# MotorControllerMainBoard.net
KiCad netlist of a schematic drawn in EAGLE
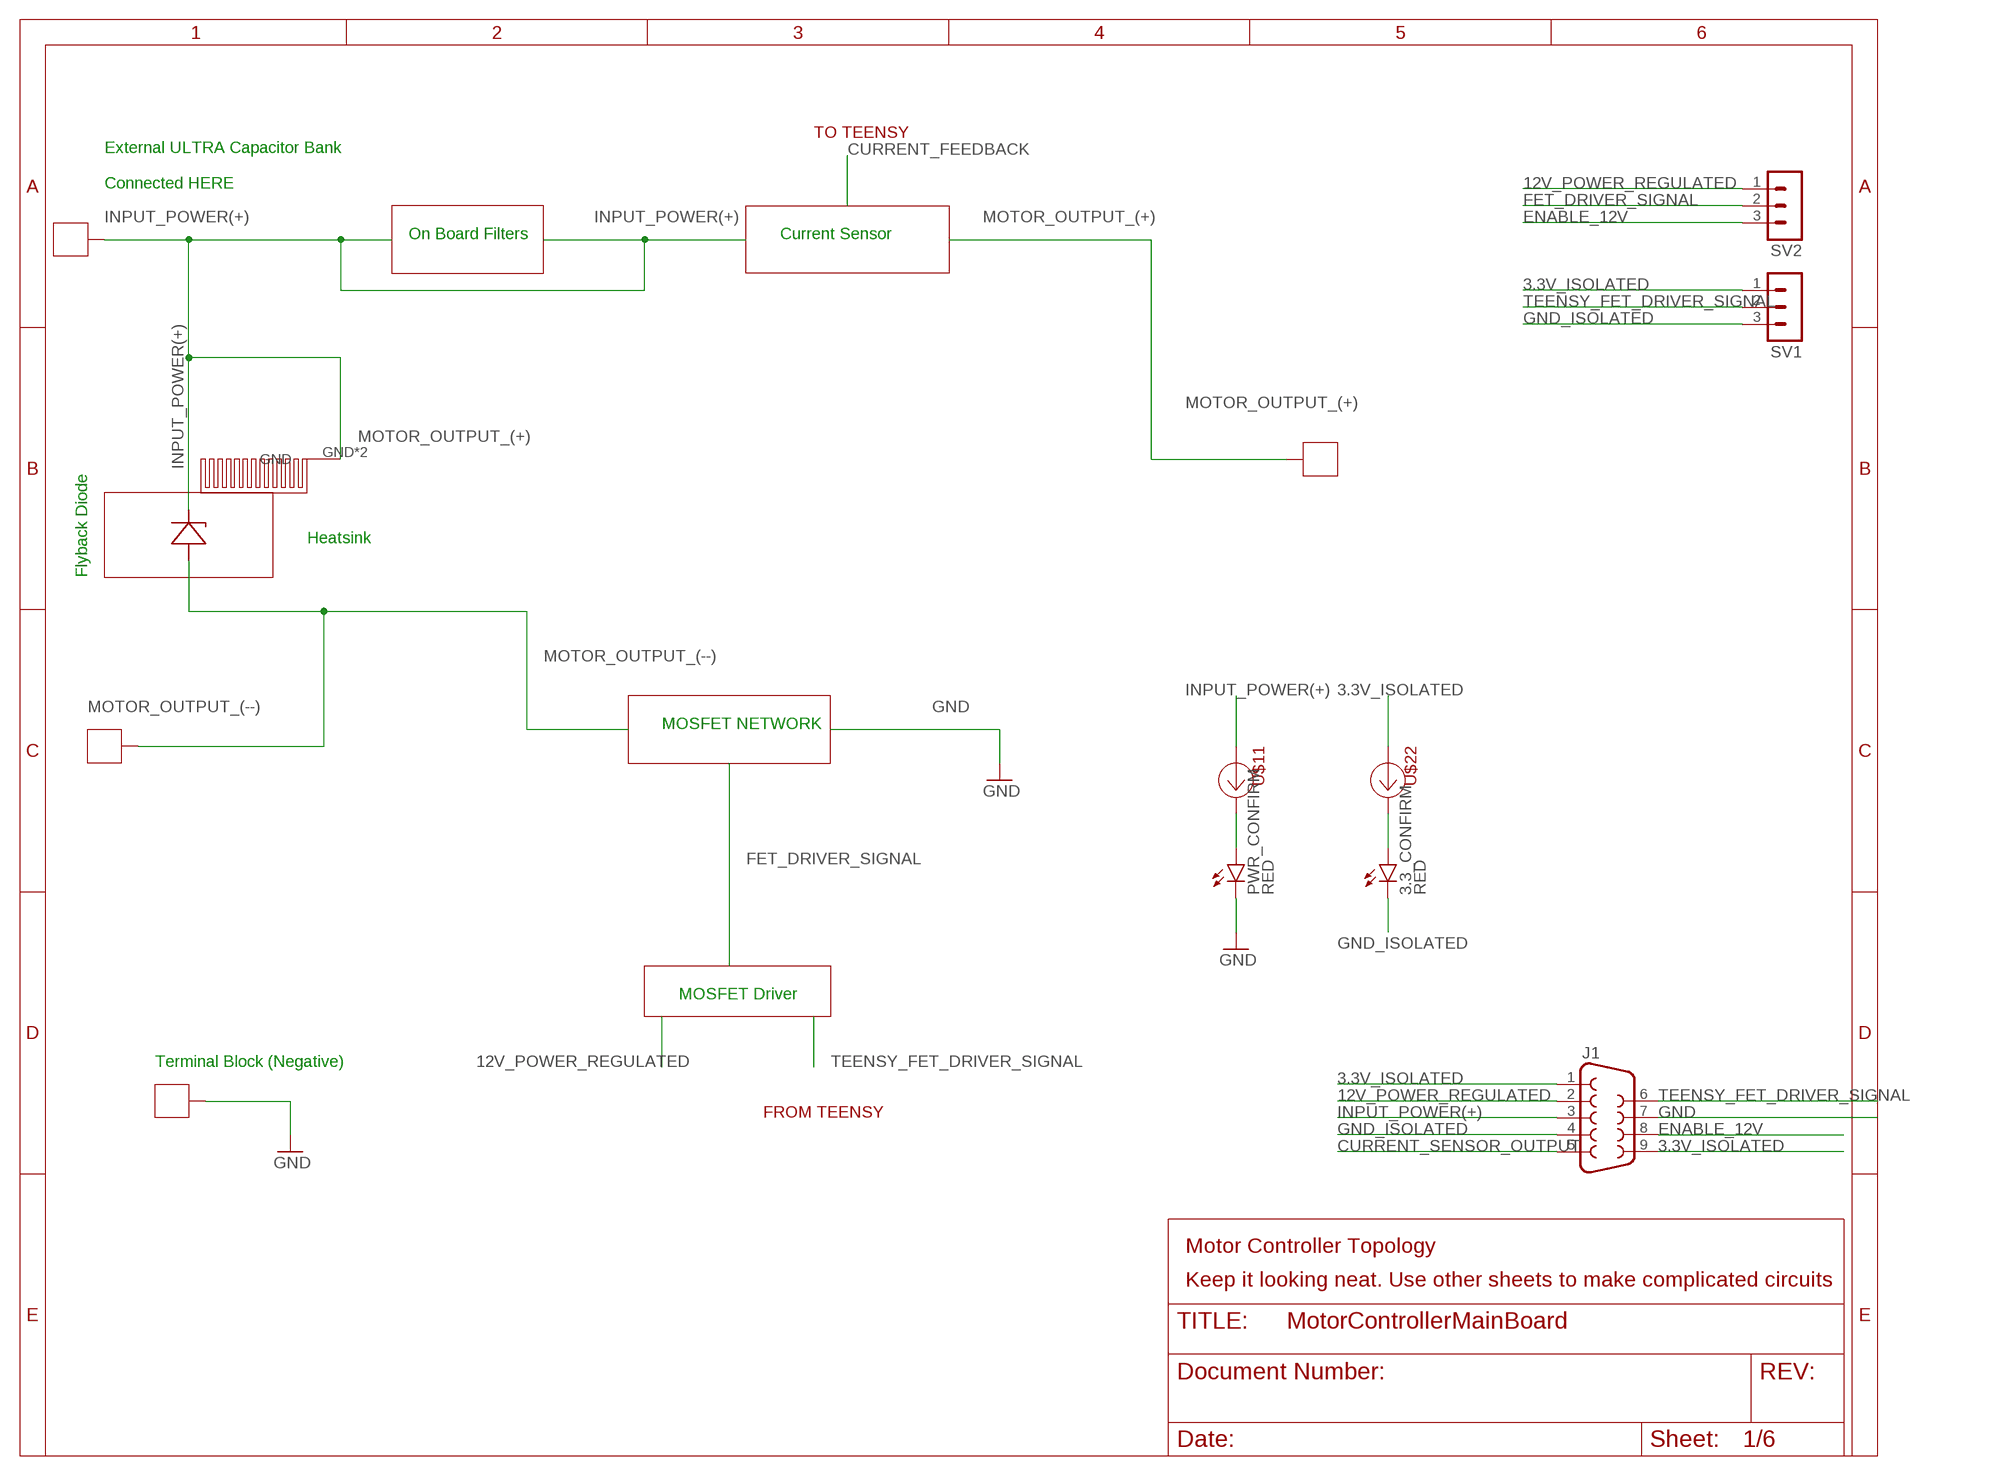
[diagram p0: schematic, sheet 1]
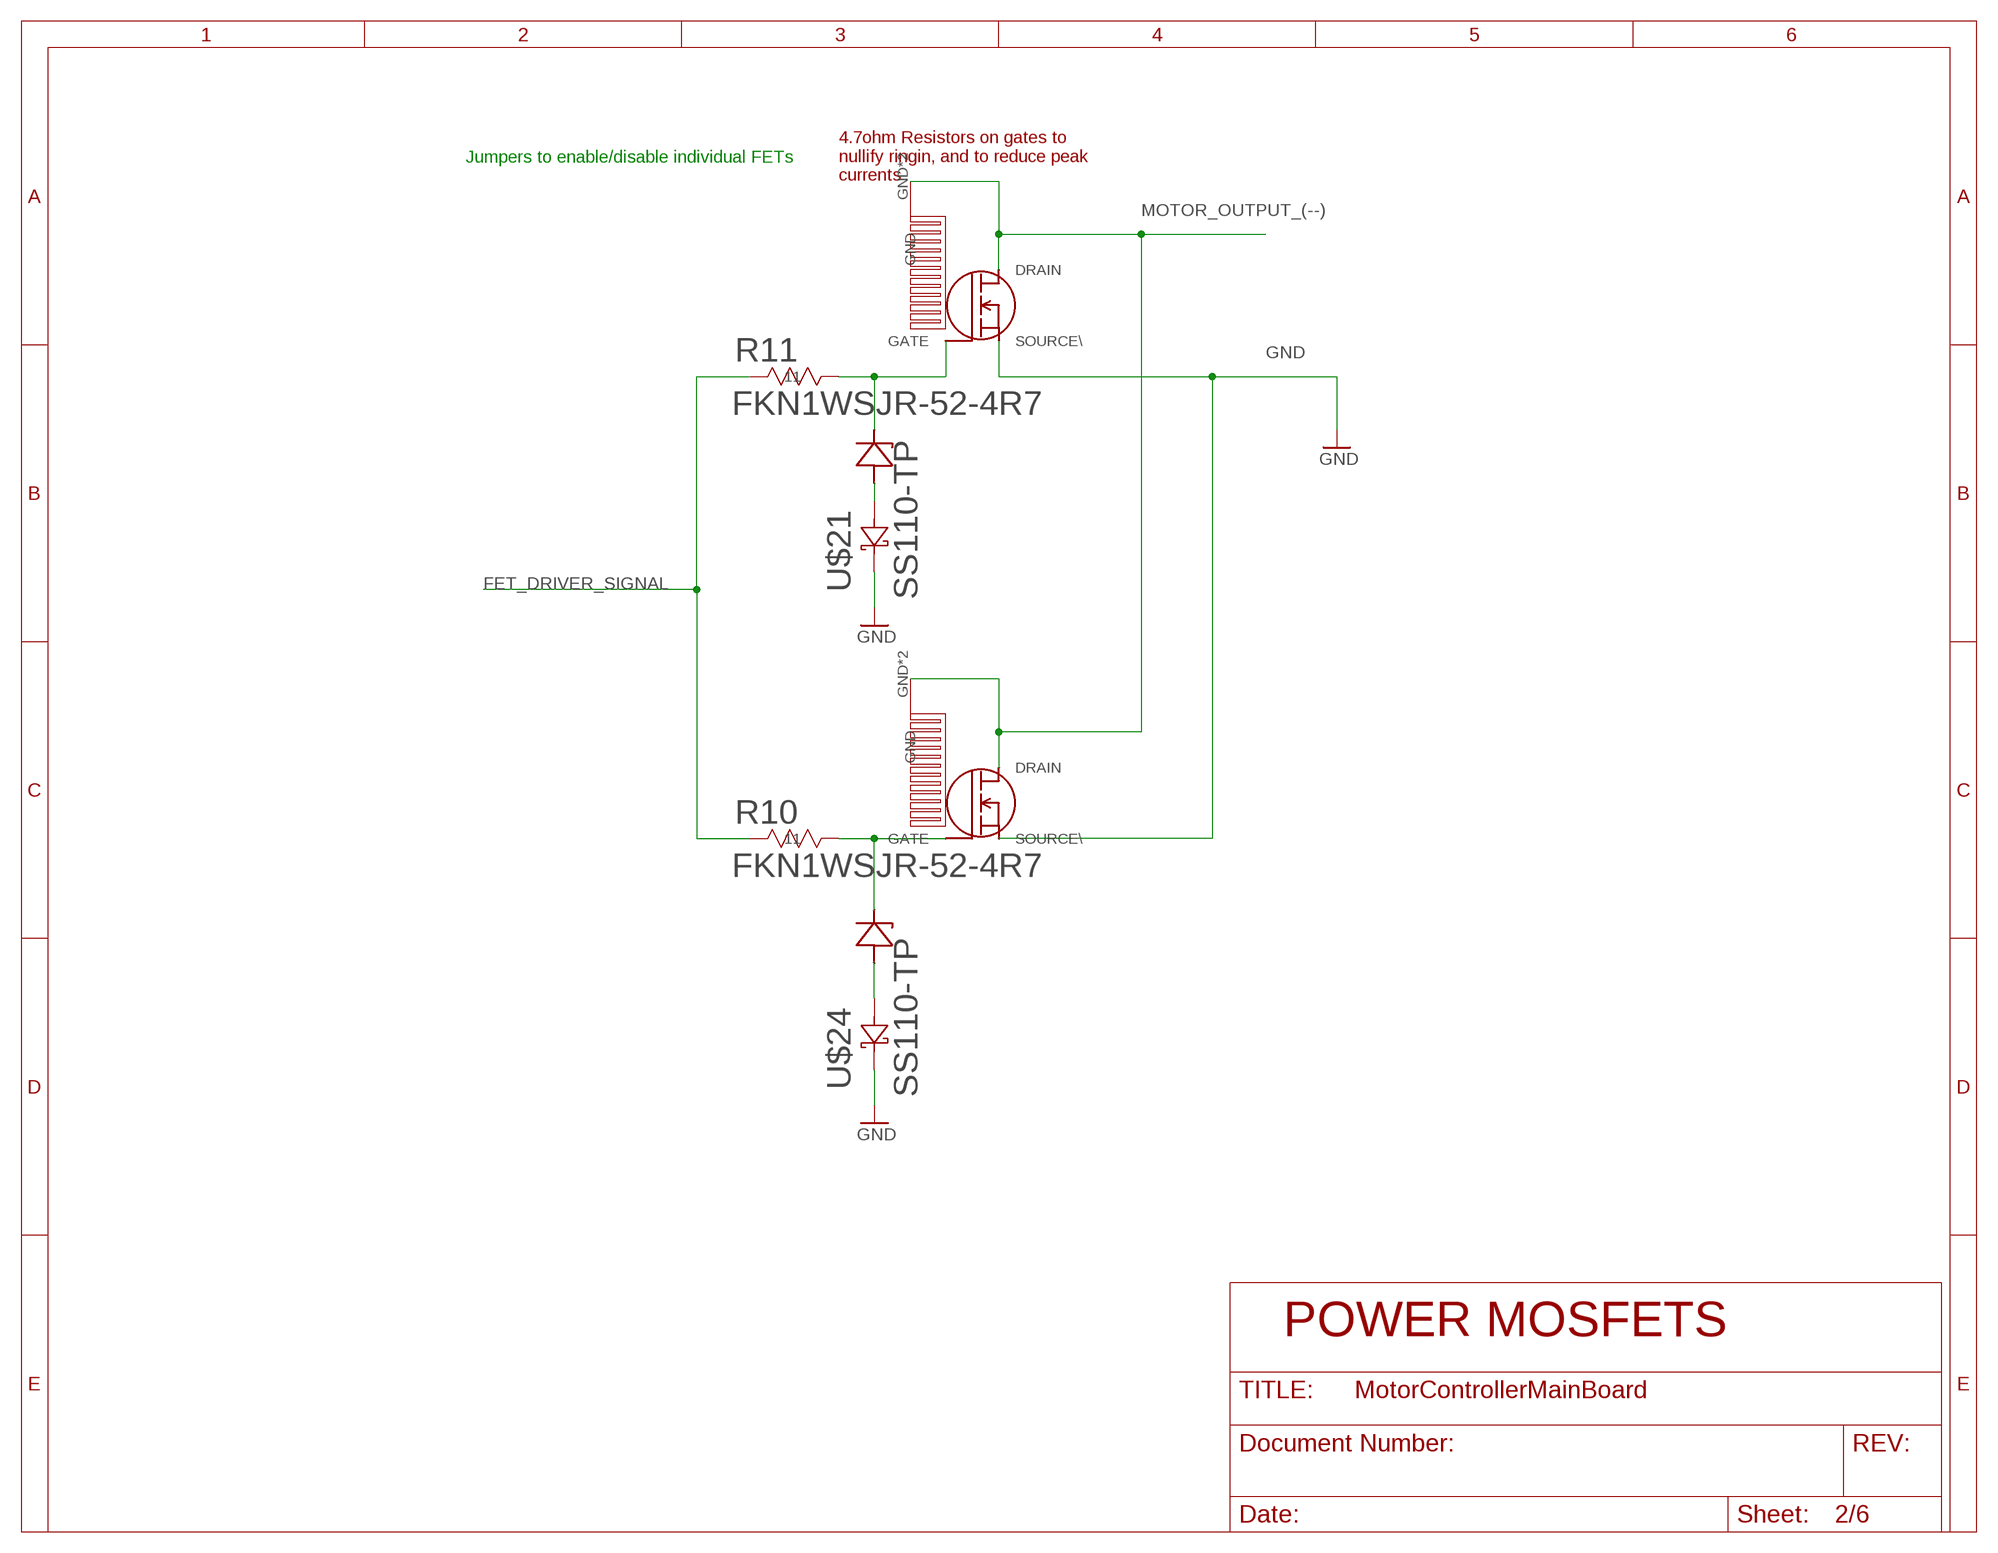
[diagram p1: schematic, sheet 2]
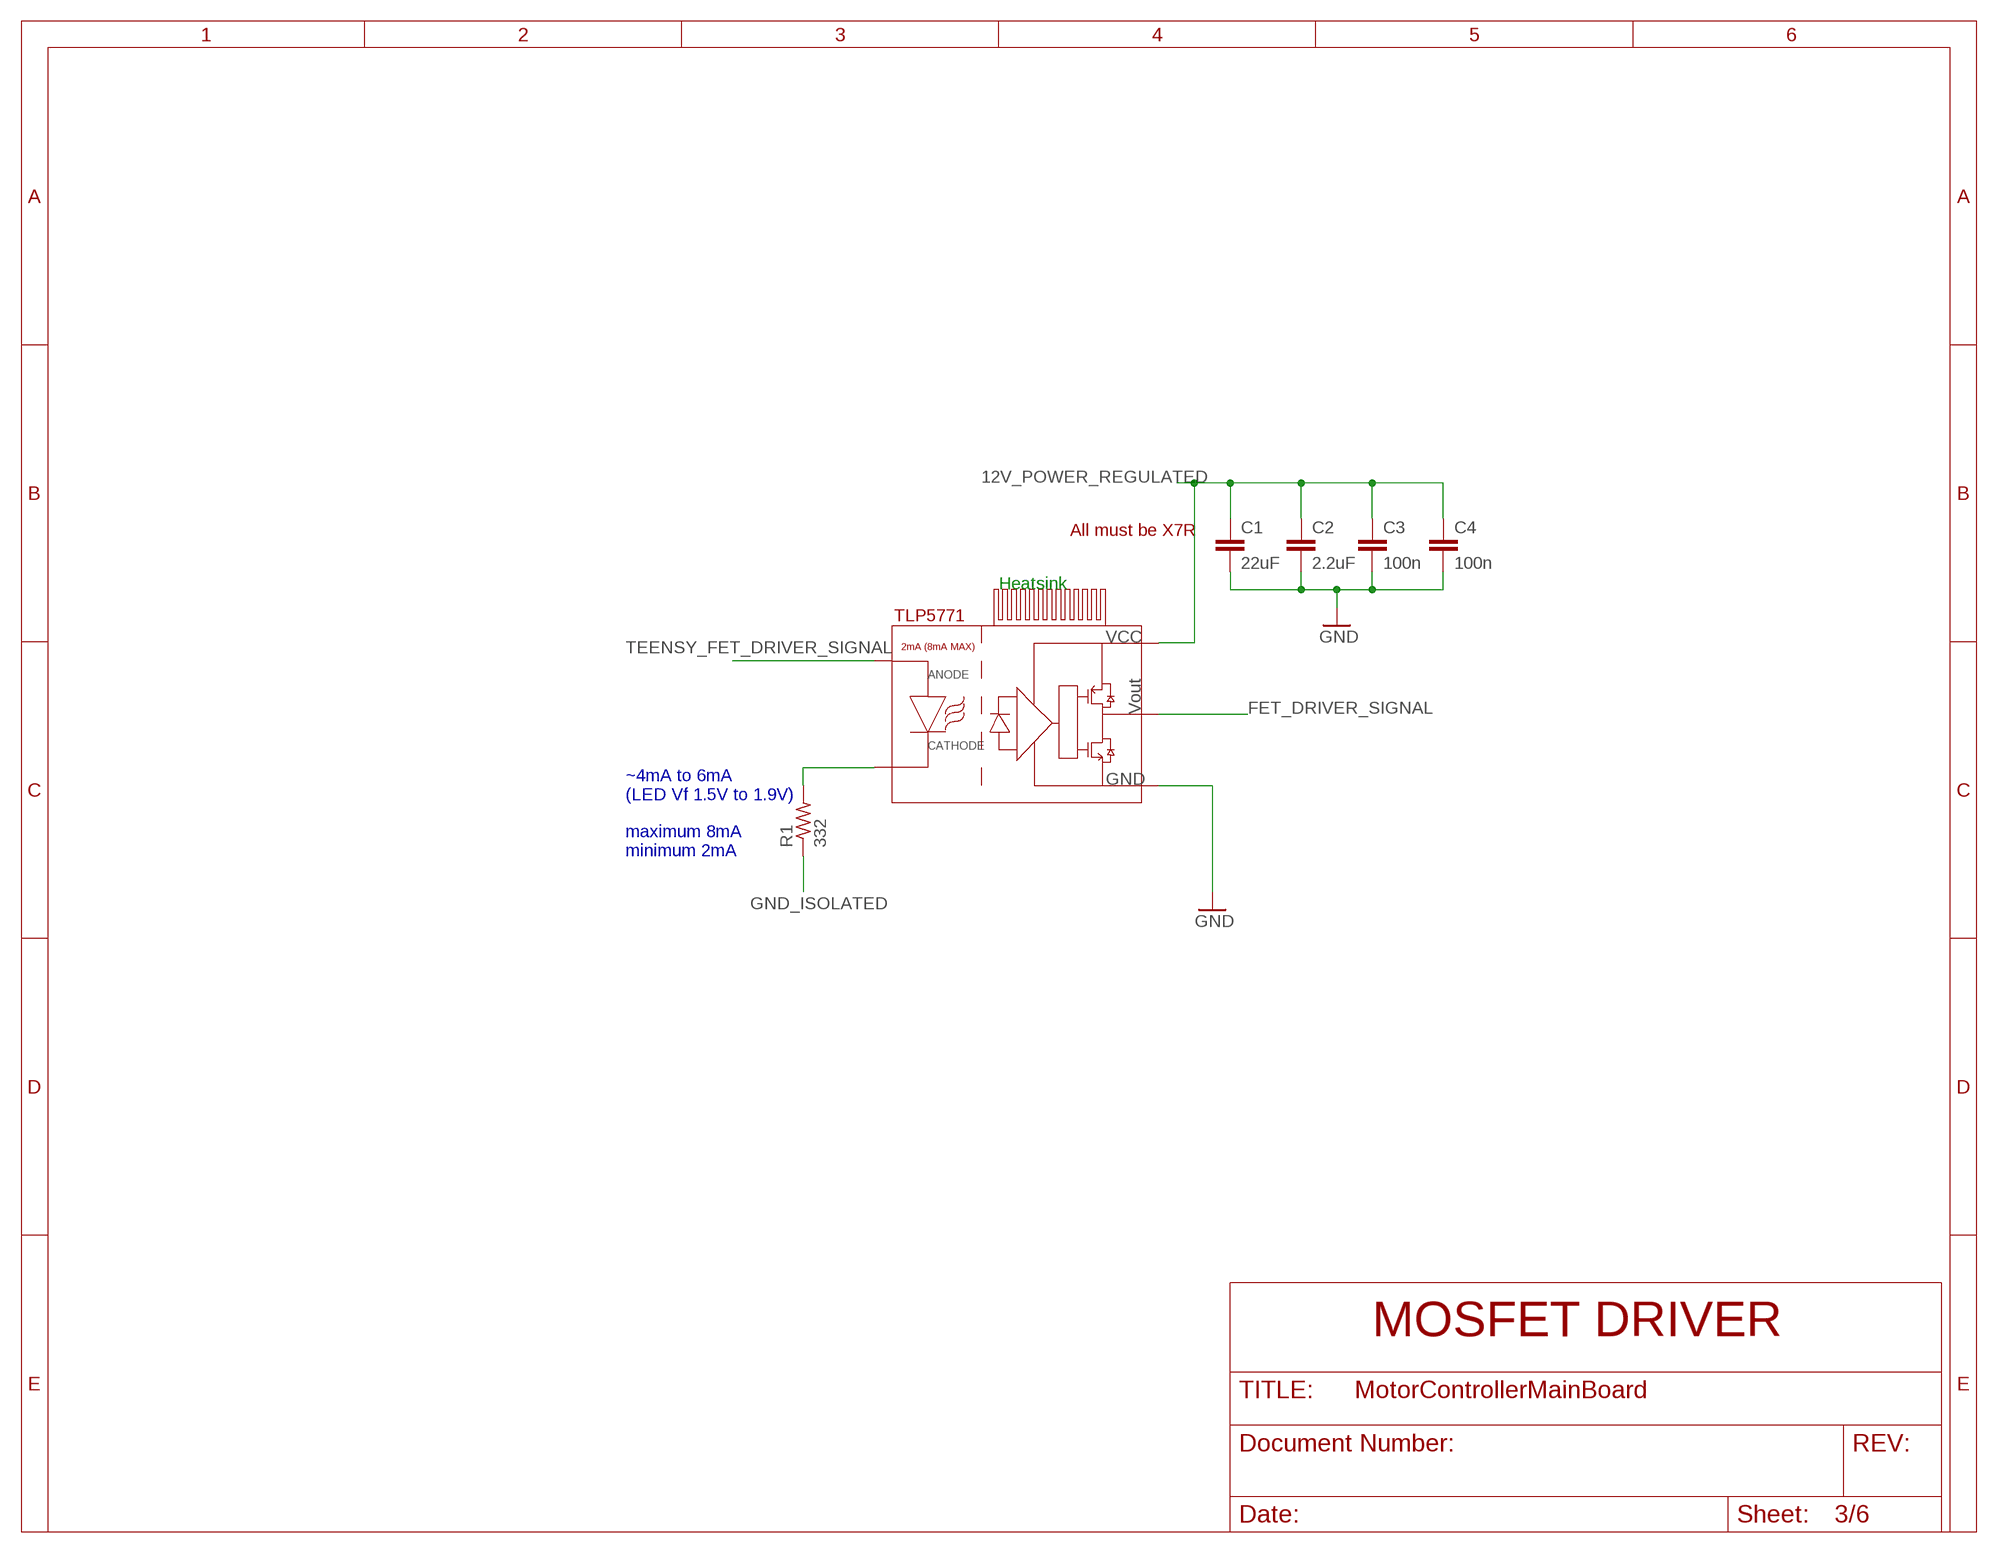
[diagram p2: schematic, sheet 3]
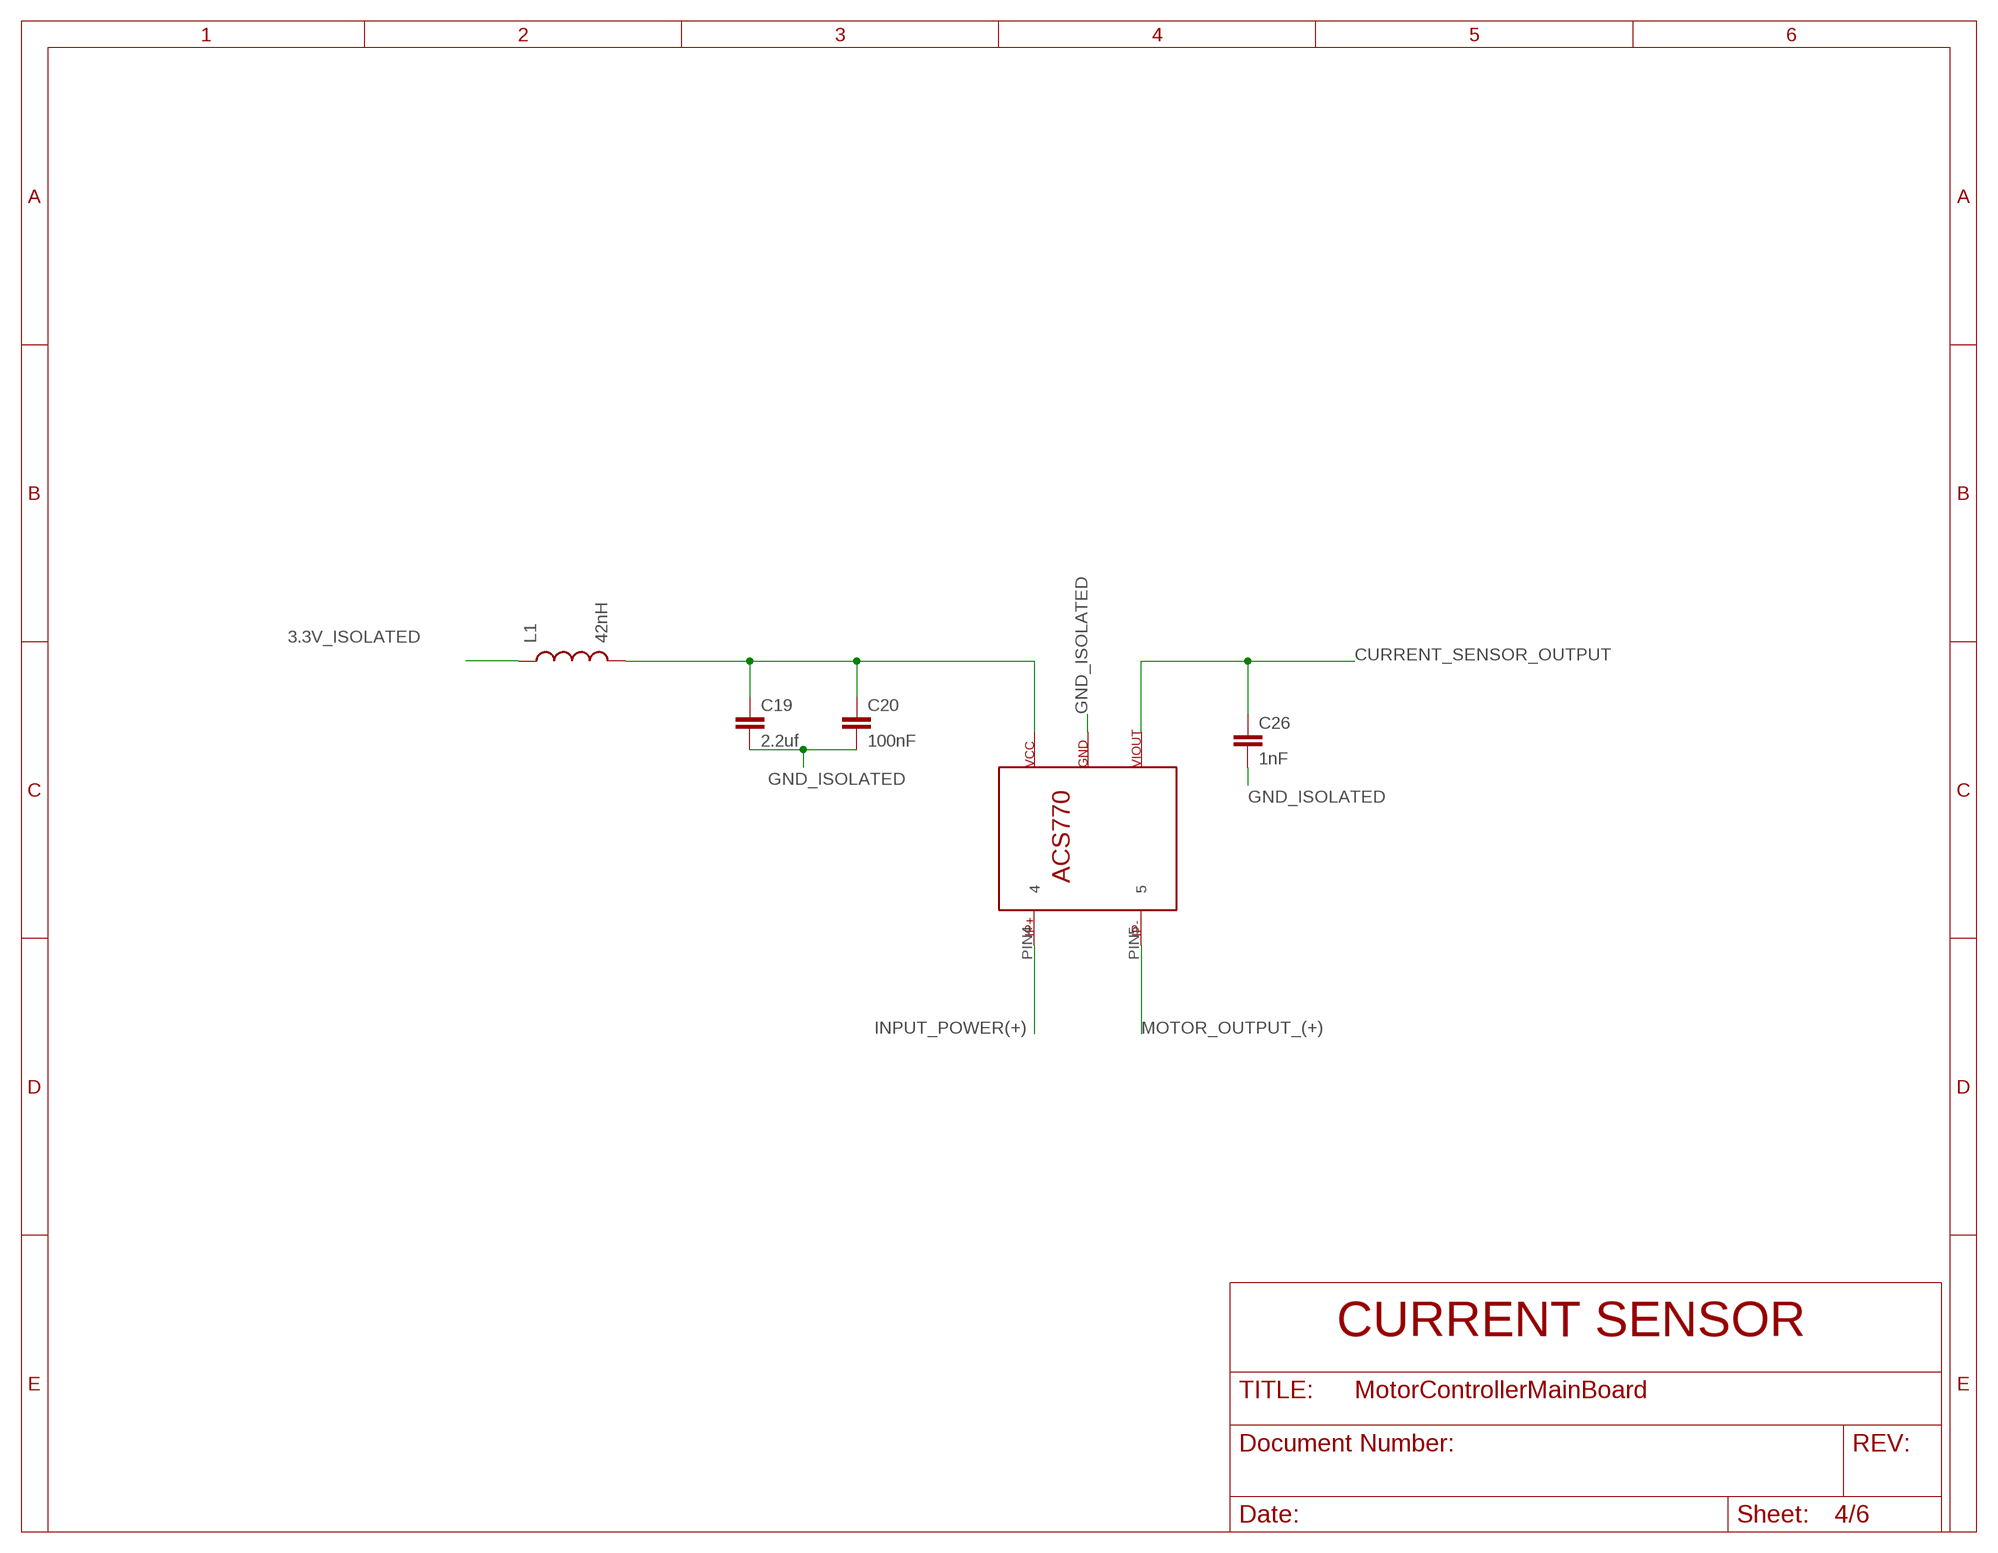
[diagram p3: schematic, sheet 4]
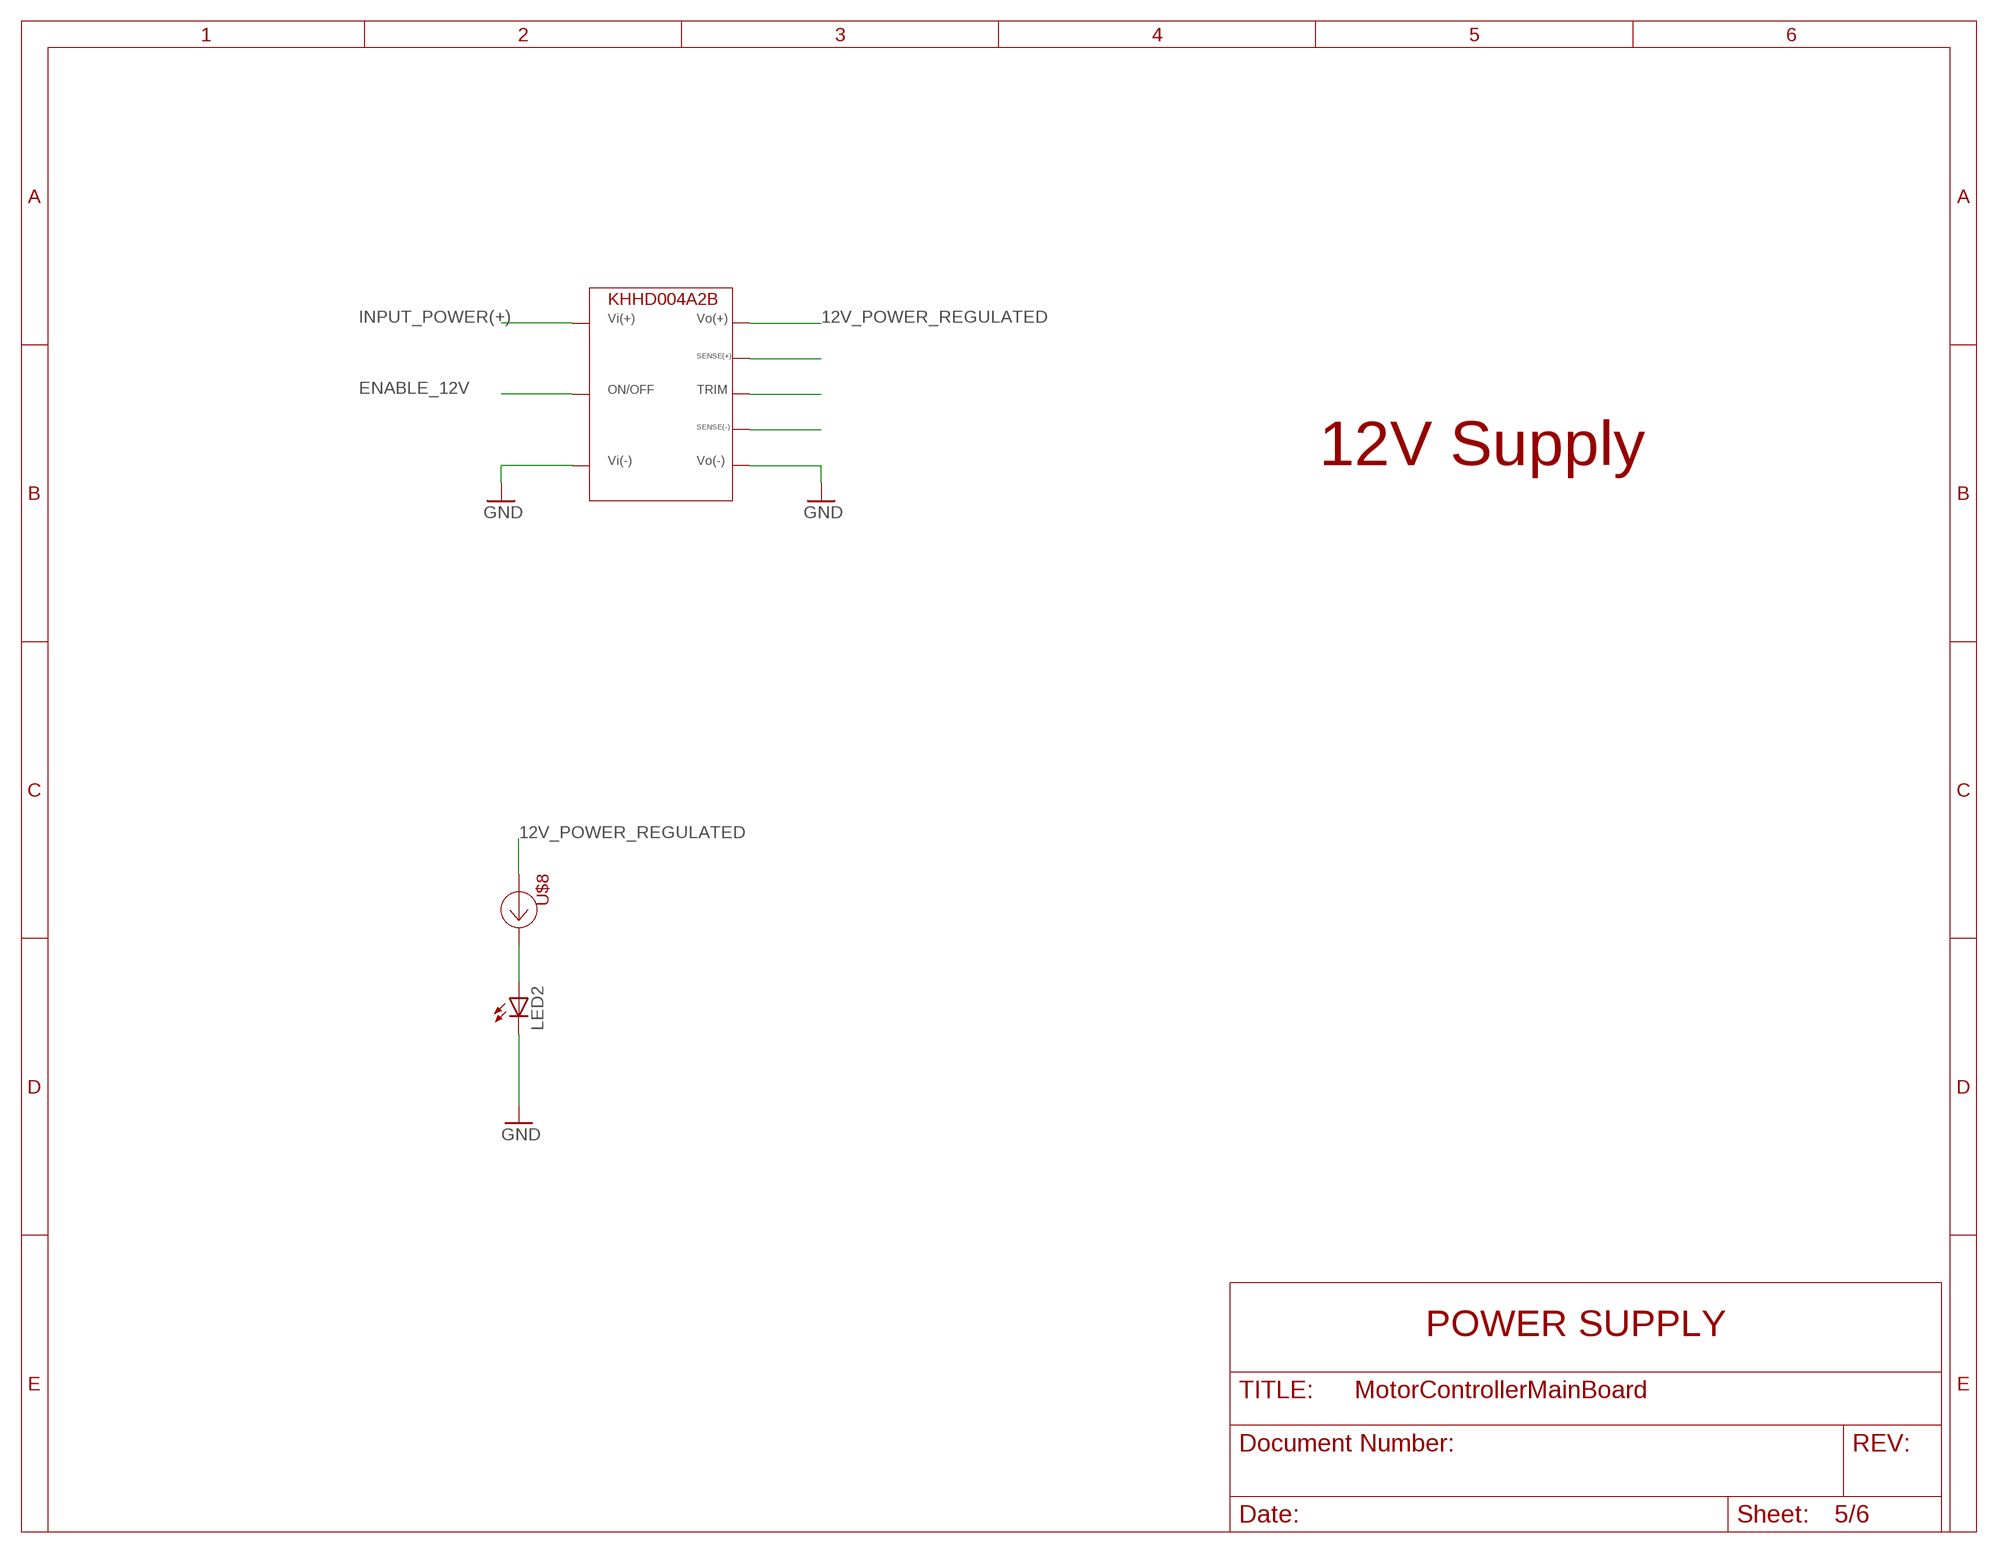
[diagram p4: schematic, sheet 5]
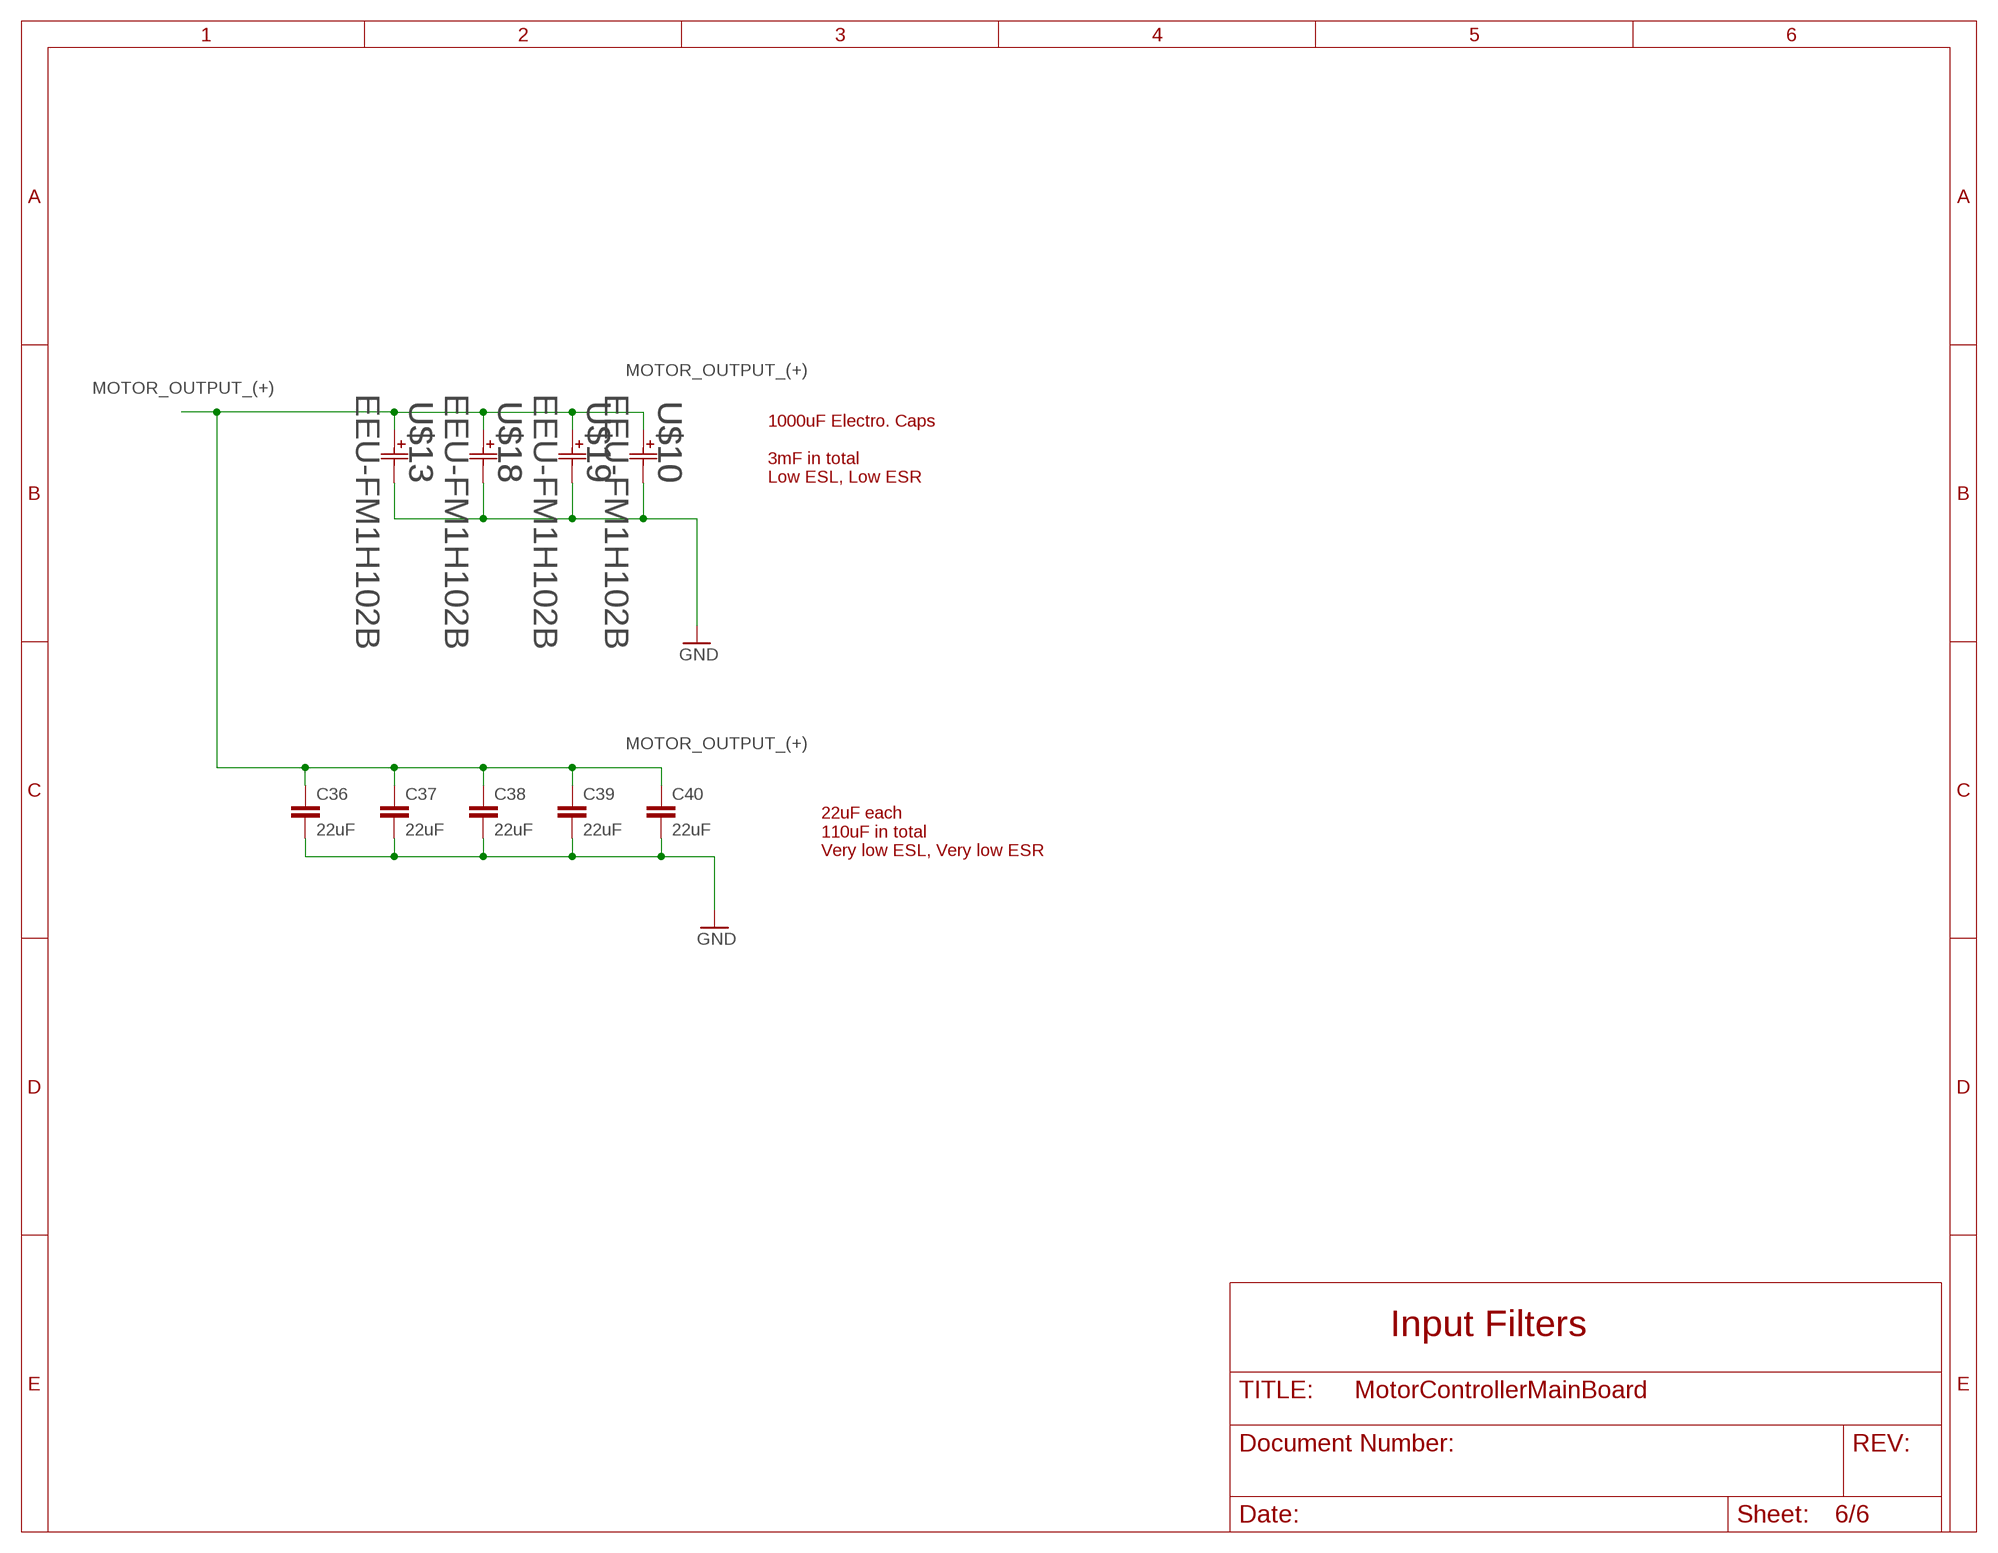
[diagram p5: schematic, sheet 6]

(export (version "E")
  (design (tool "Eeschema 10.0.6"))
  (components
    (comp (ref "3.3_CONFIRM")
      (value "RED")
      (footprint "eagle-import:LED-1206")
      (libsource (lib "eagle-import") (part "LED-RED1206"))
    )
    (comp (ref "J1")
      (value "DB9FEMALE")
      (footprint "eagle-import:DB9")
      (libsource (lib "eagle-import") (part "DB9FEMALE"))
    )
    (comp (ref "PWR_CONFIRM")
      (value "RED")
      (footprint "eagle-import:LED-1206")
      (libsource (lib "eagle-import") (part "LED-RED1206"))
    )
    (comp (ref "SV1")
      (value "MA03-1")
      (footprint "eagle-import:MA03-1")
      (libsource (lib "eagle-import") (part "MA03-1"))
    )
    (comp (ref "SV2")
      (value "MA03-1")
      (footprint "eagle-import:MA03-1")
      (libsource (lib "eagle-import") (part "MA03-1"))
    )
    (comp (ref "U$5")
      (value "FLYBACK")
      (footprint "eagle-import:TO")
      (libsource (lib "eagle-import") (part "FLYBACK"))
    )
    (comp (ref "U$11")
      (value "AL5809-20S1-7")
      (footprint "eagle-import:SOD-123")
      (libsource (lib "eagle-import") (part "AL5809-20S1-7"))
    )
    (comp (ref "U$12")
      (value "74650073R")
      (footprint "eagle-import:74650073R")
      (libsource (lib "eagle-import") (part "74650073R"))
    )
    (comp (ref "U$14")
      (value "74650073R")
      (footprint "eagle-import:74650073R")
      (libsource (lib "eagle-import") (part "74650073R"))
    )
    (comp (ref "U$15")
      (value "74650073R")
      (footprint "eagle-import:74650073R")
      (libsource (lib "eagle-import") (part "74650073R"))
    )
    (comp (ref "U$16")
      (value "74650073R")
      (footprint "eagle-import:74650073R")
      (libsource (lib "eagle-import") (part "74650073R"))
    )
    (comp (ref "U$22")
      (value "AL5809-20S1-7")
      (footprint "eagle-import:SOD-123")
      (libsource (lib "eagle-import") (part "AL5809-20S1-7"))
    )
    (comp (ref "U$23")
      (value "DA-T263-101E")
      (footprint "eagle-import:DA-T263-101E")
      (libsource (lib "eagle-import") (part "DA-T263-101E"))
    )
    (comp (ref "C36")
      (value "22uF")
      (footprint "eagle-import:C1210")
      (libsource (lib "eagle-import") (part "C-EUC1210"))
    )
    (comp (ref "C37")
      (value "22uF")
      (footprint "eagle-import:C1210")
      (libsource (lib "eagle-import") (part "C-EUC1210"))
    )
    (comp (ref "C38")
      (value "22uF")
      (footprint "eagle-import:C1210")
      (libsource (lib "eagle-import") (part "C-EUC1210"))
    )
    (comp (ref "C39")
      (value "22uF")
      (footprint "eagle-import:C1210")
      (libsource (lib "eagle-import") (part "C-EUC1210"))
    )
    (comp (ref "C40")
      (value "22uF")
      (footprint "eagle-import:C1210")
      (libsource (lib "eagle-import") (part "C-EUC1210"))
    )
    (comp (ref "U$10")
      (value "EEU-FM1H102B")
      (footprint "eagle-import:EEU-FM1H102B")
      (libsource (lib "eagle-import") (part "EEU-FM1H102B"))
    )
    (comp (ref "U$13")
      (value "EEU-FM1H102B")
      (footprint "eagle-import:EEU-FM1H102B")
      (libsource (lib "eagle-import") (part "EEU-FM1H102B"))
    )
    (comp (ref "U$18")
      (value "EEU-FM1H102B")
      (footprint "eagle-import:EEU-FM1H102B")
      (libsource (lib "eagle-import") (part "EEU-FM1H102B"))
    )
    (comp (ref "U$19")
      (value "EEU-FM1H102B")
      (footprint "eagle-import:EEU-FM1H102B")
      (libsource (lib "eagle-import") (part "EEU-FM1H102B"))
    )
    (comp (ref "LED2")
      (value "LED1206")
      (footprint "eagle-import:LED-1206")
      (libsource (lib "eagle-import") (part "LED1206"))
    )
    (comp (ref "U$6")
      (value "KHHD004A2B")
      (footprint "eagle-import:KHHD004A2B")
      (libsource (lib "eagle-import") (part "KHHD004A2B"))
    )
    (comp (ref "U$8")
      (value "AL5809-20S1-7")
      (footprint "eagle-import:SOD-123")
      (libsource (lib "eagle-import") (part "AL5809-20S1-7"))
    )
    (comp (ref "C1")
      (value "22uF")
      (footprint "eagle-import:C1210")
      (libsource (lib "eagle-import") (part "C-EUC1210"))
    )
    (comp (ref "C2")
      (value "2.2uF")
      (footprint "eagle-import:C0805")
      (libsource (lib "eagle-import") (part "C-EUC0805"))
    )
    (comp (ref "C3")
      (value "100n")
      (footprint "eagle-import:C0603")
      (libsource (lib "eagle-import") (part "C-EUC0603"))
    )
    (comp (ref "C4")
      (value "100n")
      (footprint "eagle-import:C0603")
      (libsource (lib "eagle-import") (part "C-EUC0603"))
    )
    (comp (ref "R1")
      (value "332")
      (footprint "eagle-import:R0805")
      (libsource (lib "eagle-import") (part "R-US_R0805"))
    )
    (comp (ref "U$17")
      (value "TLP5771")
      (footprint "eagle-import:SOIC-6(TLP5771)")
      (libsource (lib "eagle-import") (part "TLP5771"))
    )
    (comp (ref "U$25")
      (value "LTN20069")
      (footprint "eagle-import:LTN20069")
      (libsource (lib "eagle-import") (part "LTN20069"))
    )
    (comp (ref "C19")
      (value "2.2uf")
      (footprint "eagle-import:C0805")
      (libsource (lib "eagle-import") (part "resistor_348_C-EUC0805"))
    )
    (comp (ref "C20")
      (value "100nF")
      (footprint "eagle-import:C0805")
      (libsource (lib "eagle-import") (part "resistor_348_C-EUC0805"))
    )
    (comp (ref "C26")
      (value "1nF")
      (footprint "eagle-import:C0805")
      (libsource (lib "eagle-import") (part "resistor_348_C-EUC0805"))
    )
    (comp (ref "L1")
      (value "42nH")
      (footprint "eagle-import:0805")
      (libsource (lib "eagle-import") (part "INDUCTOR0805"))
    )
    (comp (ref "U$9")
      (value "ACS770LCB_CURRENTSENSOR")
      (footprint "eagle-import:ACS770LCB_CURRENTSENSOR")
      (libsource (lib "eagle-import") (part "ACS770LCB_CURRENTSENSOR"))
    )
    (comp (ref "R10")
      (value "FKN1WSJR-52-4R7")
      (footprint "eagle-import:YAG_FKN50")
      (fields (field (name "MANUFACTURER_PART_NUMBER") "FKN1WSJR524R7"))
      (libsource (lib "eagle-import") (part "FKN1WSJR-52-4R7"))
    )
    (comp (ref "R11")
      (value "FKN1WSJR-52-4R7")
      (footprint "eagle-import:YAG_FKN50")
      (fields (field (name "MANUFACTURER_PART_NUMBER") "FKN1WSJR524R7"))
      (libsource (lib "eagle-import") (part "FKN1WSJR-52-4R7"))
    )
    (comp (ref "U$1")
      (value "IPB015N08N5ATMA1")
      (footprint "eagle-import:IPB015N08N5ATMA1")
      (libsource (lib "eagle-import") (part "IPB015N08N5ATMA1"))
    )
    (comp (ref "U$2")
      (value "IPB015N08N5ATMA1")
      (footprint "eagle-import:IPB015N08N5ATMA1")
      (libsource (lib "eagle-import") (part "IPB015N08N5ATMA1"))
    )
    (comp (ref "U$3")
      (value "DA-T263-101E")
      (footprint "eagle-import:DA-T263-101E")
      (libsource (lib "eagle-import") (part "DA-T263-101E"))
    )
    (comp (ref "U$4")
      (value "DA-T263-101E")
      (footprint "eagle-import:DA-T263-101E")
      (libsource (lib "eagle-import") (part "DA-T263-101E"))
    )
    (comp (ref "U$7")
      (value "SMBJ15CD")
      (footprint "eagle-import:SMB-DIODE")
      (libsource (lib "eagle-import") (part "SMBJ15CD"))
    )
    (comp (ref "U$20")
      (value "SMBJ15CD")
      (footprint "eagle-import:SMB-DIODE")
      (libsource (lib "eagle-import") (part "SMBJ15CD"))
    )
    (comp (ref "U$21")
      (value "SS110-TP")
      (footprint "eagle-import:SMA-DIODE")
      (libsource (lib "eagle-import") (part "SS110-TP"))
    )
    (comp (ref "U$24")
      (value "SS110-TP")
      (footprint "eagle-import:SMA-DIODE")
      (libsource (lib "eagle-import") (part "SS110-TP"))
    )
  )
  (nets
    (net (code "1") (name "3.3V_ISOLATED") (class "Default")
      (node (ref "J1") (pin "1") (pinfunction "1_1") (pintype "passive"))
      (node (ref "J1") (pin "9") (pinfunction "9_9") (pintype "passive"))
      (node (ref "L1") (pin "1") (pinfunction "1_1") (pintype "passive"))
      (node (ref "SV1") (pin "1") (pinfunction "1_1") (pintype "passive"))
      (node (ref "U$22") (pin "A") (pinfunction "A_A") (pintype "bidirectional"))
    )
    (net (code "2") (name "12V_POWER_REGULATED") (class "Default")
      (node (ref "C1") (pin "1") (pinfunction "1_1") (pintype "passive"))
      (node (ref "C2") (pin "1") (pinfunction "1_1") (pintype "passive"))
      (node (ref "C3") (pin "1") (pinfunction "1_1") (pintype "passive"))
      (node (ref "C4") (pin "1") (pinfunction "1_1") (pintype "passive"))
      (node (ref "J1") (pin "2") (pinfunction "2_2") (pintype "passive"))
      (node (ref "SV2") (pin "1") (pinfunction "1_1") (pintype "passive"))
      (node (ref "U$17") (pin "6.VCC") (pinfunction "6.VCC_6.VCC") (pintype "bidirectional"))
      (node (ref "U$6") (pin "VO+") (pinfunction "VO(+)_VO+") (pintype "bidirectional"))
      (node (ref "U$8") (pin "A") (pinfunction "A_A") (pintype "bidirectional"))
    )
    (net (code "4") (name "CURRENT_SENSOR_OUTPUT") (class "Default")
      (node (ref "C26") (pin "1") (pinfunction "1_1") (pintype "passive"))
      (node (ref "J1") (pin "5") (pinfunction "5_5") (pintype "passive"))
      (node (ref "U$9") (pin "PIN3") (pinfunction "3_PIN3") (pintype "bidirectional"))
    )
    (net (code "5") (name "ENABLE_12V") (class "Default")
      (node (ref "J1") (pin "8") (pinfunction "8_8") (pintype "passive"))
      (node (ref "SV2") (pin "3") (pinfunction "3_3") (pintype "passive"))
      (node (ref "U$6") (pin "ON/OFF") (pinfunction "ON/OFF_ON/OFF") (pintype "bidirectional"))
    )
    (net (code "6") (name "FET_DRIVER_SIGNAL") (class "Default")
      (node (ref "R10") (pin "1") (pinfunction "11_1") (pintype "passive"))
      (node (ref "R11") (pin "1") (pinfunction "11_1") (pintype "passive"))
      (node (ref "SV2") (pin "2") (pinfunction "2_2") (pintype "passive"))
      (node (ref "U$17") (pin "5.VOUT") (pinfunction "5.VOUT_5.VOUT") (pintype "bidirectional"))
    )
    (net (code "7") (name "GND") (class "Default")
      (node (ref "C1") (pin "2") (pinfunction "2_2") (pintype "passive"))
      (node (ref "C2") (pin "2") (pinfunction "2_2") (pintype "passive"))
      (node (ref "C3") (pin "2") (pinfunction "2_2") (pintype "passive"))
      (node (ref "C36") (pin "2") (pinfunction "2_2") (pintype "passive"))
      (node (ref "C37") (pin "2") (pinfunction "2_2") (pintype "passive"))
      (node (ref "C38") (pin "2") (pinfunction "2_2") (pintype "passive"))
      (node (ref "C39") (pin "2") (pinfunction "2_2") (pintype "passive"))
      (node (ref "C4") (pin "2") (pinfunction "2_2") (pintype "passive"))
      (node (ref "C40") (pin "2") (pinfunction "2_2") (pintype "passive"))
      (node (ref "J1") (pin "7") (pinfunction "7_7") (pintype "passive"))
      (node (ref "LED2") (pin "C") (pinfunction "C_C") (pintype "passive"))
      (node (ref "PWR_CONFIRM") (pin "C") (pinfunction "C_C") (pintype "passive"))
      (node (ref "U$1") (pin "SOURCE") (pinfunction "SOURCE\\_SOURCE") (pintype "bidirectional"))
      (node (ref "U$10") (pin "NEGATIVE") (pinfunction "NEGATIVE_NEGATIVE") (pintype "passive"))
      (node (ref "U$13") (pin "NEGATIVE") (pinfunction "NEGATIVE_NEGATIVE") (pintype "passive"))
      (node (ref "U$15") (pin "P$1") (pinfunction "P$1_P$1") (pintype "bidirectional"))
      (node (ref "U$15") (pin "P$2") (pinfunction "P$1_P$2") (pintype "bidirectional"))
      (node (ref "U$15") (pin "P$3") (pinfunction "P$1_P$3") (pintype "bidirectional"))
      (node (ref "U$15") (pin "P$4") (pinfunction "P$1_P$4") (pintype "bidirectional"))
      (node (ref "U$17") (pin "4.GND") (pinfunction "4.GND_4.GND") (pintype "bidirectional"))
      (node (ref "U$18") (pin "NEGATIVE") (pinfunction "NEGATIVE_NEGATIVE") (pintype "passive"))
      (node (ref "U$19") (pin "NEGATIVE") (pinfunction "NEGATIVE_NEGATIVE") (pintype "passive"))
      (node (ref "U$2") (pin "SOURCE") (pinfunction "SOURCE\\_SOURCE") (pintype "bidirectional"))
      (node (ref "U$21") (pin "C") (pinfunction "CATHODE_C") (pintype "passive"))
      (node (ref "U$24") (pin "C") (pinfunction "CATHODE_C") (pintype "passive"))
      (node (ref "U$6") (pin "VI-") (pinfunction "VI(-)_VI-") (pintype "bidirectional"))
      (node (ref "U$6") (pin "VO-") (pinfunction "VO(-)_VO-") (pintype "bidirectional"))
    )
    (net (code "8") (name "GND_ISOLATED") (class "Default")
      (node (ref "3.3_CONFIRM") (pin "C") (pinfunction "C_C") (pintype "passive"))
      (node (ref "C19") (pin "2") (pinfunction "2_2") (pintype "passive"))
      (node (ref "C20") (pin "2") (pinfunction "2_2") (pintype "passive"))
      (node (ref "C26") (pin "2") (pinfunction "2_2") (pintype "passive"))
      (node (ref "J1") (pin "4") (pinfunction "4_4") (pintype "passive"))
      (node (ref "R1") (pin "1") (pinfunction "1_1") (pintype "passive"))
      (node (ref "SV1") (pin "3") (pinfunction "3_3") (pintype "passive"))
      (node (ref "U$9") (pin "PIN2") (pinfunction "2_PIN2") (pintype "bidirectional"))
    )
    (net (code "9") (name "INPUT_POWER(+)") (class "Default")
      (node (ref "J1") (pin "3") (pinfunction "3_3") (pintype "passive"))
      (node (ref "U$11") (pin "A") (pinfunction "A_A") (pintype "bidirectional"))
      (node (ref "U$14") (pin "P$1") (pinfunction "P$1_P$1") (pintype "bidirectional"))
      (node (ref "U$14") (pin "P$2") (pinfunction "P$1_P$2") (pintype "bidirectional"))
      (node (ref "U$14") (pin "P$3") (pinfunction "P$1_P$3") (pintype "bidirectional"))
      (node (ref "U$14") (pin "P$4") (pinfunction "P$1_P$4") (pintype "bidirectional"))
      (node (ref "U$23") (pin "GND") (pinfunction "GND_GND") (pintype "bidirectional"))
      (node (ref "U$23") (pin "GND2\\") (pinfunction "GND_GND2\\") (pintype "bidirectional"))
      (node (ref "U$5") (pin "CATHODE") (pinfunction "CATHODE_CATHODE") (pintype "bidirectional"))
      (node (ref "U$6") (pin "VI+") (pinfunction "VI(+)_VI+") (pintype "bidirectional"))
      (node (ref "U$9") (pin "PIN4") (pinfunction "4_PIN4") (pintype "bidirectional"))
    )
    (net (code "10") (name "MOTOR_OUTPUT_(+)") (class "Default")
      (node (ref "C36") (pin "1") (pinfunction "1_1") (pintype "passive"))
      (node (ref "C37") (pin "1") (pinfunction "1_1") (pintype "passive"))
      (node (ref "C38") (pin "1") (pinfunction "1_1") (pintype "passive"))
      (node (ref "C39") (pin "1") (pinfunction "1_1") (pintype "passive"))
      (node (ref "C40") (pin "1") (pinfunction "1_1") (pintype "passive"))
      (node (ref "U$10") (pin "POSITIVE") (pinfunction "POSITIVE_POSITIVE") (pintype "passive"))
      (node (ref "U$13") (pin "POSITIVE") (pinfunction "POSITIVE_POSITIVE") (pintype "passive"))
      (node (ref "U$16") (pin "P$1") (pinfunction "P$1_P$1") (pintype "bidirectional"))
      (node (ref "U$16") (pin "P$2") (pinfunction "P$1_P$2") (pintype "bidirectional"))
      (node (ref "U$16") (pin "P$3") (pinfunction "P$1_P$3") (pintype "bidirectional"))
      (node (ref "U$16") (pin "P$4") (pinfunction "P$1_P$4") (pintype "bidirectional"))
      (node (ref "U$18") (pin "POSITIVE") (pinfunction "POSITIVE_POSITIVE") (pintype "passive"))
      (node (ref "U$19") (pin "POSITIVE") (pinfunction "POSITIVE_POSITIVE") (pintype "passive"))
      (node (ref "U$9") (pin "PIN5") (pinfunction "5_PIN5") (pintype "bidirectional"))
    )
    (net (code "11") (name "MOTOR_OUTPUT_(--)") (class "Default")
      (node (ref "U$1") (pin "DRAIN") (pinfunction "DRAIN_DRAIN") (pintype "bidirectional"))
      (node (ref "U$12") (pin "P$1") (pinfunction "P$1_P$1") (pintype "bidirectional"))
      (node (ref "U$12") (pin "P$2") (pinfunction "P$1_P$2") (pintype "bidirectional"))
      (node (ref "U$12") (pin "P$3") (pinfunction "P$1_P$3") (pintype "bidirectional"))
      (node (ref "U$12") (pin "P$4") (pinfunction "P$1_P$4") (pintype "bidirectional"))
      (node (ref "U$2") (pin "DRAIN") (pinfunction "DRAIN_DRAIN") (pintype "bidirectional"))
      (node (ref "U$3") (pin "GND") (pinfunction "GND_GND") (pintype "bidirectional"))
      (node (ref "U$3") (pin "GND2\\") (pinfunction "GND_GND2\\") (pintype "bidirectional"))
      (node (ref "U$4") (pin "GND") (pinfunction "GND_GND") (pintype "bidirectional"))
      (node (ref "U$4") (pin "GND2\\") (pinfunction "GND_GND2\\") (pintype "bidirectional"))
      (node (ref "U$5") (pin "ANODE") (pinfunction "ANODE_ANODE") (pintype "bidirectional"))
    )
    (net (code "12") (name "Net-(3.3_CONFIRM-PadA)") (class "Default")
      (node (ref "3.3_CONFIRM") (pin "A") (pinfunction "A_A") (pintype "passive"))
      (node (ref "U$22") (pin "C") (pinfunction "C_C") (pintype "bidirectional"))
    )
    (net (code "13") (name "Net-(LED2-PadA)") (class "Default")
      (node (ref "LED2") (pin "A") (pinfunction "A_A") (pintype "passive"))
      (node (ref "U$8") (pin "C") (pinfunction "C_C") (pintype "bidirectional"))
    )
    (net (code "14") (name "Net-(PWR_CONFIRM-PadA)") (class "Default")
      (node (ref "PWR_CONFIRM") (pin "A") (pinfunction "A_A") (pintype "passive"))
      (node (ref "U$11") (pin "C") (pinfunction "C_C") (pintype "bidirectional"))
    )
    (net (code "15") (name "Net-(R1-Pad2)") (class "Default")
      (node (ref "R1") (pin "2") (pinfunction "2_2") (pintype "passive"))
      (node (ref "U$17") (pin "2.NC") (pinfunction "3.CATHODE_2.NC") (pintype "bidirectional"))
      (node (ref "U$17") (pin "3:CATHODE") (pinfunction "3.CATHODE_3:CATHODE") (pintype "bidirectional"))
    )
    (net (code "16") (name "Net-(R10-22)") (class "Default")
      (node (ref "R10") (pin "2") (pinfunction "22_2") (pintype "passive"))
      (node (ref "U$2") (pin "GATE") (pinfunction "GATE_GATE") (pintype "bidirectional"))
      (node (ref "U$7") (pin "C") (pinfunction "CATHODE_C") (pintype "bidirectional"))
    )
    (net (code "17") (name "Net-(R11-22)") (class "Default")
      (node (ref "R11") (pin "2") (pinfunction "22_2") (pintype "passive"))
      (node (ref "U$1") (pin "GATE") (pinfunction "GATE_GATE") (pintype "bidirectional"))
      (node (ref "U$20") (pin "C") (pinfunction "CATHODE_C") (pintype "bidirectional"))
    )
    (net (code "18") (name "Net-(U$9-1)") (class "Default")
      (node (ref "C19") (pin "1") (pinfunction "1_1") (pintype "passive"))
      (node (ref "C20") (pin "1") (pinfunction "1_1") (pintype "passive"))
      (node (ref "L1") (pin "2") (pinfunction "2_2") (pintype "passive"))
      (node (ref "U$9") (pin "PIN1") (pinfunction "1_PIN1") (pintype "bidirectional"))
    )
    (net (code "19") (name "Net-(U$20-ANODE)") (class "Default")
      (node (ref "U$20") (pin "A") (pinfunction "ANODE_A") (pintype "bidirectional"))
      (node (ref "U$21") (pin "A") (pinfunction "ANODE_A") (pintype "passive"))
    )
    (net (code "20") (name "Net-(U$24-ANODE)") (class "Default")
      (node (ref "U$24") (pin "A") (pinfunction "ANODE_A") (pintype "passive"))
      (node (ref "U$7") (pin "A") (pinfunction "ANODE_A") (pintype "bidirectional"))
    )
    (net (code "21") (name "TEENSY_FET_DRIVER_SIGNAL") (class "Default")
      (node (ref "J1") (pin "6") (pinfunction "6_6") (pintype "passive"))
      (node (ref "SV1") (pin "2") (pinfunction "2_2") (pintype "passive"))
      (node (ref "U$17") (pin "1.ANODE") (pinfunction "1.ANODE_1.ANODE") (pintype "bidirectional"))
    )
    (net (code "22") (name "unconnected-(U$6-PadTRIM)") (class "Default")
      (node (ref "U$6") (pin "TRIM") (pinfunction "TRIM_TRIM") (pintype "bidirectional"))
    )
    (net (code "23") (name "unconnected-(U$6-SENSE(+)-PadSENSE+)") (class "Default")
      (node (ref "U$6") (pin "SENSE+") (pinfunction "SENSE(+)_SENSE+") (pintype "bidirectional"))
    )
    (net (code "24") (name "unconnected-(U$6-SENSE(-)-PadSENSE-)") (class "Default")
      (node (ref "U$6") (pin "SENSE-") (pinfunction "SENSE(-)_SENSE-") (pintype "bidirectional"))
    )
  )
)
